# EXP_GameDuino_V1.net
KiCad netlist of a schematic drawn in EAGLE
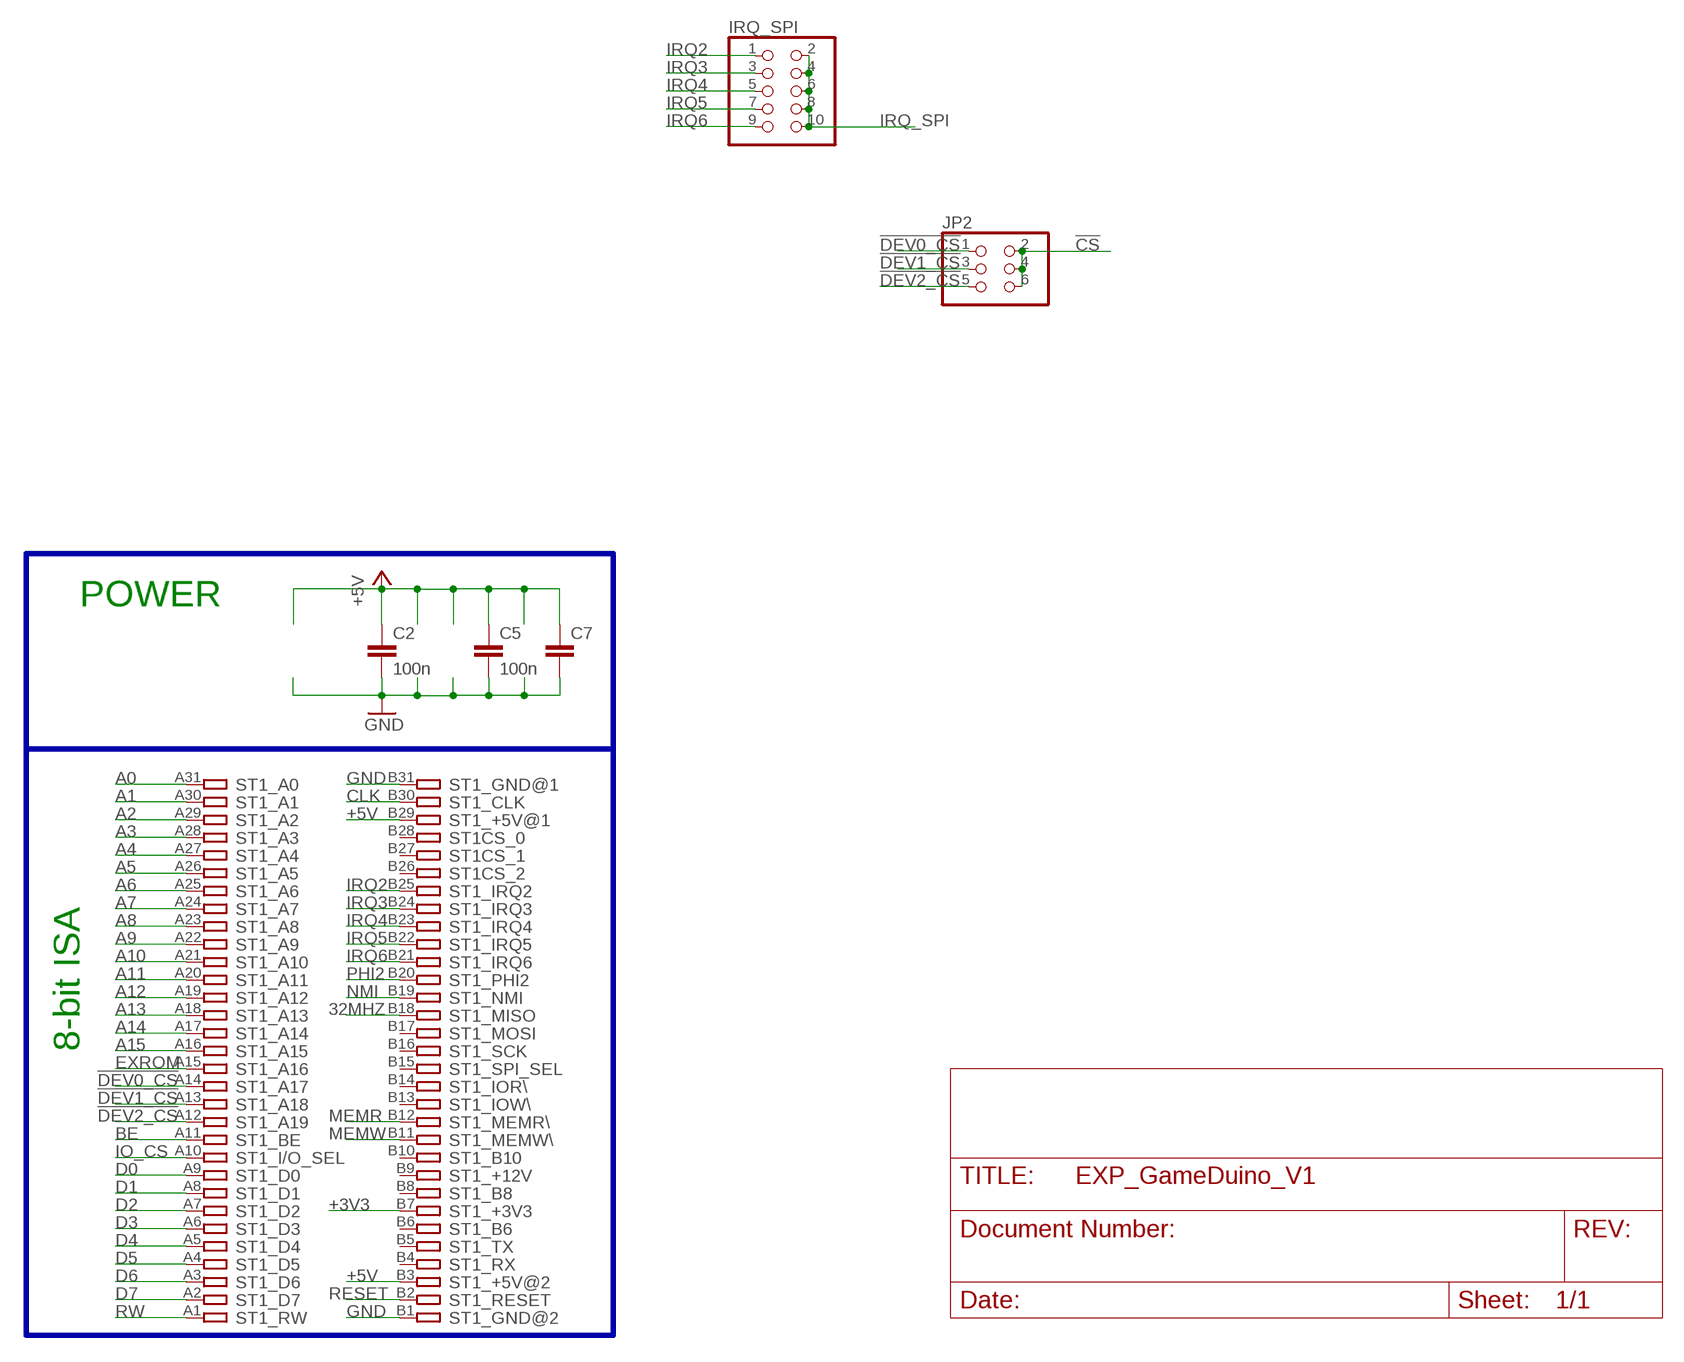
[diagram p0: schematic, sheet 1, part 1 of 2]
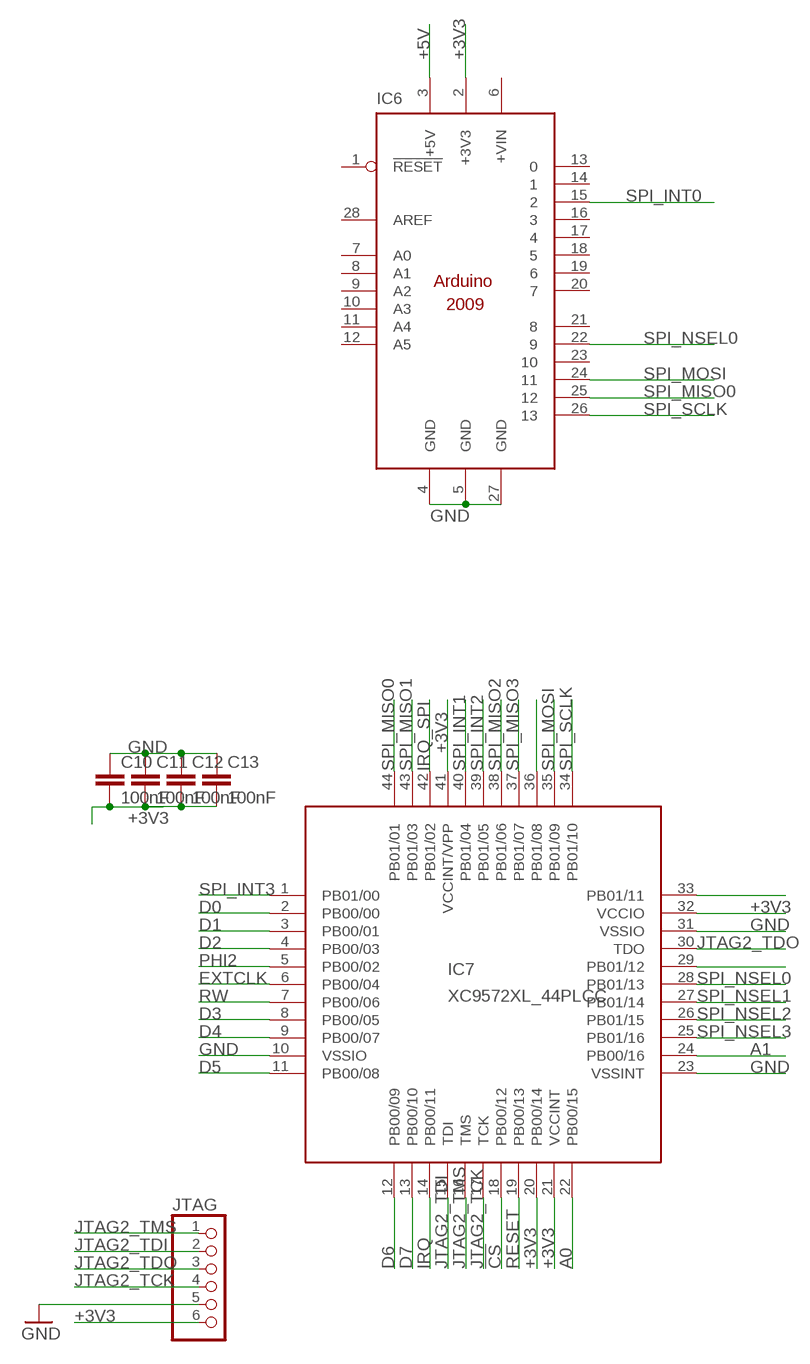
[diagram p1: schematic, sheet 1, part 2 of 2]

(export (version "E")
  (design (tool "Eeschema 10.0.6"))
  (components
    (comp (ref "C2")
      (value "100n")
      (footprint "eagle-import:C050-025X075")
      (libsource (lib "eagle-import") (part "C-EU050-025X075"))
    )
    (comp (ref "C5")
      (value "100n")
      (footprint "eagle-import:C050-025X075")
      (libsource (lib "eagle-import") (part "C-EU050-025X075"))
    )
    (comp (ref "C7")
      (value "C-EU050-035X075")
      (footprint "eagle-import:C050-035X075")
      (libsource (lib "eagle-import") (part "rcl_334_C-EU050-035X075"))
    )
    (comp (ref "C10")
      (value "100nF")
      (footprint "eagle-import:C603")
      (libsource (lib "eagle-import") (part "CAPC603"))
    )
    (comp (ref "C11")
      (value "100nF")
      (footprint "eagle-import:C603")
      (libsource (lib "eagle-import") (part "CAPC603"))
    )
    (comp (ref "C12")
      (value "100nF")
      (footprint "eagle-import:C603")
      (libsource (lib "eagle-import") (part "CAPC603"))
    )
    (comp (ref "C13")
      (value "100nF")
      (footprint "eagle-import:C603")
      (libsource (lib "eagle-import") (part "CAPC603"))
    )
    (comp (ref "IC6")
      (value "ARDUINO2009_10")
      (footprint "eagle-import:ARDUINO2009")
      (libsource (lib "eagle-import") (part "ARDUINO2009_10"))
    )
    (comp (ref "IC7")
      (value "XC9572XL_44PLCC")
      (footprint "eagle-import:S44")
      (libsource (lib "eagle-import") (part "XC9536_44PLCCPLCC44_THT"))
    )
    (comp (ref "IRQ_SPI")
      (value "PINHD-2X5")
      (footprint "eagle-import:2X05")
      (libsource (lib "eagle-import") (part "PINHD-2X5"))
    )
    (comp (ref "JP2")
      (value "PINHD-2X3")
      (footprint "eagle-import:2X03")
      (libsource (lib "eagle-import") (part "PINHD-2X3"))
    )
    (comp (ref "JTAG")
      (value "PINHD-1X6")
      (footprint "eagle-import:1X06")
      (libsource (lib "eagle-import") (part "PINHD-1X6"))
    )
    (comp (ref "ST1")
      (value "IBM8BIT_ISASHORT")
      (footprint "eagle-import:APP_2X32_SHORT")
      (libsource (lib "eagle-import") (part "IBM8BIT_ISASHORT"))
    )
  )
  (nets
    (net (code "1") (name "+5V") (class "Default")
      (node (ref "C2") (pin "1") (pinfunction "1_1") (pintype "passive"))
      (node (ref "C5") (pin "1") (pinfunction "1_1") (pintype "passive"))
      (node (ref "C7") (pin "1") (pinfunction "1_1") (pintype "passive"))
      (node (ref "IC6") (pin "3") (pinfunction "+5V_3") (pintype "power_in"))
      (node (ref "ST1") (pin "B29") (pinfunction "P_B29") (pintype "bidirectional"))
      (node (ref "ST1") (pin "B3") (pinfunction "P_B3") (pintype "bidirectional"))
    )
    (net (code "2") (name "/+3V3") (class "Default")
      (node (ref "C10") (pin "2") (pinfunction "2_2") (pintype "passive"))
      (node (ref "C11") (pin "2") (pinfunction "2_2") (pintype "passive"))
      (node (ref "C12") (pin "2") (pinfunction "2_2") (pintype "passive"))
      (node (ref "C13") (pin "2") (pinfunction "2_2") (pintype "passive"))
      (node (ref "IC6") (pin "2") (pinfunction "+3V3_2") (pintype "power_in"))
      (node (ref "IC7") (pin "20") (pinfunction "PB00/14_20") (pintype "bidirectional"))
      (node (ref "IC7") (pin "21") (pinfunction "VCCINT_21") (pintype "power_in"))
      (node (ref "IC7") (pin "32") (pinfunction "VCCIO_32") (pintype "power_in"))
      (node (ref "IC7") (pin "41") (pinfunction "VCCINT/VPP_41") (pintype "input"))
      (node (ref "JTAG") (pin "6") (pinfunction "6_6") (pintype "passive"))
      (node (ref "ST1") (pin "B7") (pinfunction "P_B7") (pintype "bidirectional"))
    )
    (net (code "3") (name "/32MHZ") (class "Default")
      (node (ref "ST1") (pin "B18") (pinfunction "P_B18") (pintype "bidirectional"))
    )
    (net (code "4") (name "/A0") (class "Default")
      (node (ref "IC7") (pin "22") (pinfunction "PB00/15_22") (pintype "bidirectional"))
      (node (ref "ST1") (pin "A31") (pinfunction "P_A31") (pintype "bidirectional"))
    )
    (net (code "5") (name "/A1") (class "Default")
      (node (ref "IC7") (pin "24") (pinfunction "PB00/16_24") (pintype "bidirectional"))
      (node (ref "ST1") (pin "A30") (pinfunction "P_A30") (pintype "bidirectional"))
    )
    (net (code "6") (name "/A2") (class "Default")
      (node (ref "ST1") (pin "A29") (pinfunction "P_A29") (pintype "bidirectional"))
    )
    (net (code "7") (name "/A3") (class "Default")
      (node (ref "ST1") (pin "A28") (pinfunction "P_A28") (pintype "bidirectional"))
    )
    (net (code "8") (name "/A4") (class "Default")
      (node (ref "ST1") (pin "A27") (pinfunction "P_A27") (pintype "bidirectional"))
    )
    (net (code "9") (name "/A5") (class "Default")
      (node (ref "ST1") (pin "A26") (pinfunction "P_A26") (pintype "bidirectional"))
    )
    (net (code "10") (name "/A6") (class "Default")
      (node (ref "ST1") (pin "A25") (pinfunction "P_A25") (pintype "bidirectional"))
    )
    (net (code "11") (name "/A7") (class "Default")
      (node (ref "ST1") (pin "A24") (pinfunction "P_A24") (pintype "bidirectional"))
    )
    (net (code "12") (name "/A8") (class "Default")
      (node (ref "ST1") (pin "A23") (pinfunction "P_A23") (pintype "bidirectional"))
    )
    (net (code "13") (name "/A9") (class "Default")
      (node (ref "ST1") (pin "A22") (pinfunction "P_A22") (pintype "bidirectional"))
    )
    (net (code "14") (name "/A10") (class "Default")
      (node (ref "ST1") (pin "A21") (pinfunction "P_A21") (pintype "bidirectional"))
    )
    (net (code "15") (name "/A11") (class "Default")
      (node (ref "ST1") (pin "A20") (pinfunction "P_A20") (pintype "bidirectional"))
    )
    (net (code "16") (name "/A12") (class "Default")
      (node (ref "ST1") (pin "A19") (pinfunction "P_A19") (pintype "bidirectional"))
    )
    (net (code "17") (name "/A13") (class "Default")
      (node (ref "ST1") (pin "A18") (pinfunction "P_A18") (pintype "bidirectional"))
    )
    (net (code "18") (name "/A14") (class "Default")
      (node (ref "ST1") (pin "A17") (pinfunction "P_A17") (pintype "bidirectional"))
    )
    (net (code "19") (name "/A15") (class "Default")
      (node (ref "ST1") (pin "A16") (pinfunction "P_A16") (pintype "bidirectional"))
    )
    (net (code "20") (name "/BE") (class "Default")
      (node (ref "ST1") (pin "A11") (pinfunction "P_A11") (pintype "bidirectional"))
    )
    (net (code "21") (name "/CLK") (class "Default")
      (node (ref "ST1") (pin "B30") (pinfunction "P_B30") (pintype "bidirectional"))
    )
    (net (code "22") (name "/D0") (class "Default")
      (node (ref "IC7") (pin "2") (pinfunction "PB00/00_2") (pintype "bidirectional"))
      (node (ref "ST1") (pin "A9") (pinfunction "P_A9") (pintype "bidirectional"))
    )
    (net (code "23") (name "/D1") (class "Default")
      (node (ref "IC7") (pin "3") (pinfunction "PB00/01_3") (pintype "bidirectional"))
      (node (ref "ST1") (pin "A8") (pinfunction "P_A8") (pintype "bidirectional"))
    )
    (net (code "24") (name "/D2") (class "Default")
      (node (ref "IC7") (pin "4") (pinfunction "PB00/03_4") (pintype "bidirectional"))
      (node (ref "ST1") (pin "A7") (pinfunction "P_A7") (pintype "bidirectional"))
    )
    (net (code "25") (name "/D3") (class "Default")
      (node (ref "IC7") (pin "8") (pinfunction "PB00/05_8") (pintype "bidirectional"))
      (node (ref "ST1") (pin "A6") (pinfunction "P_A6") (pintype "bidirectional"))
    )
    (net (code "26") (name "/D4") (class "Default")
      (node (ref "IC7") (pin "9") (pinfunction "PB00/07_9") (pintype "bidirectional"))
      (node (ref "ST1") (pin "A5") (pinfunction "P_A5") (pintype "bidirectional"))
    )
    (net (code "27") (name "/D5") (class "Default")
      (node (ref "IC7") (pin "11") (pinfunction "PB00/08_11") (pintype "bidirectional"))
      (node (ref "ST1") (pin "A4") (pinfunction "P_A4") (pintype "bidirectional"))
    )
    (net (code "28") (name "/D6") (class "Default")
      (node (ref "IC7") (pin "12") (pinfunction "PB00/09_12") (pintype "bidirectional"))
      (node (ref "ST1") (pin "A3") (pinfunction "P_A3") (pintype "bidirectional"))
    )
    (net (code "29") (name "/D7") (class "Default")
      (node (ref "IC7") (pin "13") (pinfunction "PB00/10_13") (pintype "bidirectional"))
      (node (ref "ST1") (pin "A2") (pinfunction "P_A2") (pintype "bidirectional"))
    )
    (net (code "30") (name "/EXROM") (class "Default")
      (node (ref "ST1") (pin "A15") (pinfunction "P_A15") (pintype "bidirectional"))
    )
    (net (code "31") (name "/EXTCLK") (class "Default")
      (node (ref "IC7") (pin "6") (pinfunction "PB00/04_6") (pintype "bidirectional"))
    )
    (net (code "32") (name "/IO_CS") (class "Default")
      (node (ref "ST1") (pin "A10") (pinfunction "P_A10") (pintype "bidirectional"))
    )
    (net (code "33") (name "/IRQ") (class "Default")
      (node (ref "IC7") (pin "14") (pinfunction "PB00/11_14") (pintype "bidirectional"))
    )
    (net (code "34") (name "/IRQ2") (class "Default")
      (node (ref "IRQ_SPI") (pin "1") (pinfunction "1_1") (pintype "passive"))
      (node (ref "ST1") (pin "B25") (pinfunction "P_B25") (pintype "bidirectional"))
    )
    (net (code "35") (name "/IRQ3") (class "Default")
      (node (ref "IRQ_SPI") (pin "3") (pinfunction "3_3") (pintype "passive"))
      (node (ref "ST1") (pin "B24") (pinfunction "P_B24") (pintype "bidirectional"))
    )
    (net (code "36") (name "/IRQ4") (class "Default")
      (node (ref "IRQ_SPI") (pin "5") (pinfunction "5_5") (pintype "passive"))
      (node (ref "ST1") (pin "B23") (pinfunction "P_B23") (pintype "bidirectional"))
    )
    (net (code "37") (name "/IRQ5") (class "Default")
      (node (ref "IRQ_SPI") (pin "7") (pinfunction "7_7") (pintype "passive"))
      (node (ref "ST1") (pin "B22") (pinfunction "P_B22") (pintype "bidirectional"))
    )
    (net (code "38") (name "/IRQ6") (class "Default")
      (node (ref "IRQ_SPI") (pin "9") (pinfunction "9_9") (pintype "passive"))
      (node (ref "ST1") (pin "B21") (pinfunction "P_B21") (pintype "bidirectional"))
    )
    (net (code "39") (name "/IRQ_SPI") (class "Default")
      (node (ref "IC7") (pin "42") (pinfunction "PB01/02_42") (pintype "bidirectional"))
      (node (ref "IRQ_SPI") (pin "10") (pinfunction "10_10") (pintype "passive"))
      (node (ref "IRQ_SPI") (pin "2") (pinfunction "2_2") (pintype "passive"))
      (node (ref "IRQ_SPI") (pin "4") (pinfunction "4_4") (pintype "passive"))
      (node (ref "IRQ_SPI") (pin "6") (pinfunction "6_6") (pintype "passive"))
      (node (ref "IRQ_SPI") (pin "8") (pinfunction "8_8") (pintype "passive"))
    )
    (net (code "40") (name "/JTAG2_TCK") (class "Default")
      (node (ref "IC7") (pin "17") (pinfunction "TCK_17") (pintype "input"))
      (node (ref "JTAG") (pin "4") (pinfunction "4_4") (pintype "passive"))
    )
    (net (code "41") (name "/JTAG2_TDI") (class "Default")
      (node (ref "IC7") (pin "15") (pinfunction "TDI_15") (pintype "input"))
      (node (ref "JTAG") (pin "2") (pinfunction "2_2") (pintype "passive"))
    )
    (net (code "42") (name "/JTAG2_TDO") (class "Default")
      (node (ref "IC7") (pin "30") (pinfunction "TDO_30") (pintype "output"))
      (node (ref "JTAG") (pin "3") (pinfunction "3_3") (pintype "passive"))
    )
    (net (code "43") (name "/JTAG2_TMS") (class "Default")
      (node (ref "IC7") (pin "16") (pinfunction "TMS_16") (pintype "input"))
      (node (ref "JTAG") (pin "1") (pinfunction "1_1") (pintype "passive"))
    )
    (net (code "44") (name "/MEMR") (class "Default")
      (node (ref "ST1") (pin "B12") (pinfunction "P_B12") (pintype "bidirectional"))
    )
    (net (code "45") (name "/MEMW") (class "Default")
      (node (ref "ST1") (pin "B11") (pinfunction "P_B11") (pintype "bidirectional"))
    )
    (net (code "46") (name "/NMI") (class "Default")
      (node (ref "ST1") (pin "B19") (pinfunction "P_B19") (pintype "bidirectional"))
    )
    (net (code "47") (name "/PHI2") (class "Default")
      (node (ref "IC7") (pin "5") (pinfunction "PB00/02_5") (pintype "bidirectional"))
      (node (ref "ST1") (pin "B20") (pinfunction "P_B20") (pintype "bidirectional"))
    )
    (net (code "48") (name "/RESET") (class "Default")
      (node (ref "IC7") (pin "19") (pinfunction "PB00/13_19") (pintype "bidirectional"))
      (node (ref "ST1") (pin "B2") (pinfunction "P_B2") (pintype "bidirectional"))
    )
    (net (code "49") (name "/RW") (class "Default")
      (node (ref "IC7") (pin "7") (pinfunction "PB00/06_7") (pintype "bidirectional"))
      (node (ref "ST1") (pin "A1") (pinfunction "P_A1") (pintype "bidirectional"))
    )
    (net (code "50") (name "/SPI_INT0") (class "Default")
      (node (ref "IC6") (pin "15") (pinfunction "2_15") (pintype "bidirectional"))
    )
    (net (code "51") (name "/SPI_INT1") (class "Default")
      (node (ref "IC7") (pin "40") (pinfunction "PB01/04_40") (pintype "bidirectional"))
    )
    (net (code "52") (name "/SPI_INT2") (class "Default")
      (node (ref "IC7") (pin "39") (pinfunction "PB01/05_39") (pintype "bidirectional"))
    )
    (net (code "53") (name "/SPI_INT3") (class "Default")
      (node (ref "IC7") (pin "1") (pinfunction "PB01/00_1") (pintype "bidirectional"))
    )
    (net (code "54") (name "/SPI_MISO0") (class "Default")
      (node (ref "IC6") (pin "25") (pinfunction "12_25") (pintype "bidirectional"))
      (node (ref "IC7") (pin "44") (pinfunction "PB01/01_44") (pintype "bidirectional"))
    )
    (net (code "55") (name "/SPI_MISO1") (class "Default")
      (node (ref "IC7") (pin "43") (pinfunction "PB01/03_43") (pintype "bidirectional"))
    )
    (net (code "56") (name "/SPI_MISO2") (class "Default")
      (node (ref "IC7") (pin "38") (pinfunction "PB01/06_38") (pintype "bidirectional"))
    )
    (net (code "57") (name "/SPI_MISO3") (class "Default")
      (node (ref "IC7") (pin "37") (pinfunction "PB01/07_37") (pintype "bidirectional"))
    )
    (net (code "58") (name "/SPI_MOSI") (class "Default")
      (node (ref "IC6") (pin "24") (pinfunction "11_24") (pintype "bidirectional"))
      (node (ref "IC7") (pin "35") (pinfunction "PB01/09_35") (pintype "bidirectional"))
    )
    (net (code "59") (name "/SPI_NSEL0") (class "Default")
      (node (ref "IC6") (pin "22") (pinfunction "9_22") (pintype "bidirectional"))
      (node (ref "IC7") (pin "28") (pinfunction "PB01/13_28") (pintype "bidirectional"))
    )
    (net (code "60") (name "/SPI_NSEL1") (class "Default")
      (node (ref "IC7") (pin "27") (pinfunction "PB01/14_27") (pintype "bidirectional"))
    )
    (net (code "61") (name "/SPI_NSEL2") (class "Default")
      (node (ref "IC7") (pin "26") (pinfunction "PB01/15_26") (pintype "bidirectional"))
    )
    (net (code "62") (name "/SPI_NSEL3") (class "Default")
      (node (ref "IC7") (pin "25") (pinfunction "PB01/16_25") (pintype "bidirectional"))
    )
    (net (code "63") (name "/SPI_SCLK") (class "Default")
      (node (ref "IC6") (pin "26") (pinfunction "13_26") (pintype "bidirectional"))
      (node (ref "IC7") (pin "34") (pinfunction "PB01/10_34") (pintype "bidirectional"))
    )
    (net (code "64") (name "/~{CS}") (class "Default")
      (node (ref "IC7") (pin "18") (pinfunction "PB00/12_18") (pintype "bidirectional"))
      (node (ref "JP2") (pin "2") (pinfunction "2_2") (pintype "passive"))
      (node (ref "JP2") (pin "4") (pinfunction "4_4") (pintype "passive"))
      (node (ref "JP2") (pin "6") (pinfunction "6_6") (pintype "passive"))
    )
    (net (code "65") (name "/~{DEV0_CS}") (class "Default")
      (node (ref "JP2") (pin "1") (pinfunction "1_1") (pintype "passive"))
      (node (ref "ST1") (pin "A14") (pinfunction "P_A14") (pintype "bidirectional"))
    )
    (net (code "66") (name "/~{DEV1_CS}") (class "Default")
      (node (ref "JP2") (pin "3") (pinfunction "3_3") (pintype "passive"))
      (node (ref "ST1") (pin "A13") (pinfunction "P_A13") (pintype "bidirectional"))
    )
    (net (code "67") (name "/~{DEV2_CS}") (class "Default")
      (node (ref "JP2") (pin "5") (pinfunction "5_5") (pintype "passive"))
      (node (ref "ST1") (pin "A12") (pinfunction "P_A12") (pintype "bidirectional"))
    )
    (net (code "68") (name "GND") (class "Default")
      (node (ref "C10") (pin "1") (pinfunction "1_1") (pintype "passive"))
      (node (ref "C11") (pin "1") (pinfunction "1_1") (pintype "passive"))
      (node (ref "C12") (pin "1") (pinfunction "1_1") (pintype "passive"))
      (node (ref "C13") (pin "1") (pinfunction "1_1") (pintype "passive"))
      (node (ref "C2") (pin "2") (pinfunction "2_2") (pintype "passive"))
      (node (ref "C5") (pin "2") (pinfunction "2_2") (pintype "passive"))
      (node (ref "C7") (pin "2") (pinfunction "2_2") (pintype "passive"))
      (node (ref "IC6") (pin "27") (pinfunction "GND_27") (pintype "power_in"))
      (node (ref "IC6") (pin "4") (pinfunction "GND_4") (pintype "power_in"))
      (node (ref "IC6") (pin "5") (pinfunction "GND_5") (pintype "power_in"))
      (node (ref "IC7") (pin "10") (pinfunction "VSSIO_10") (pintype "power_in"))
      (node (ref "IC7") (pin "23") (pinfunction "VSSINT_23") (pintype "power_in"))
      (node (ref "IC7") (pin "31") (pinfunction "VSSIO_31") (pintype "power_in"))
      (node (ref "JTAG") (pin "5") (pinfunction "5_5") (pintype "passive"))
      (node (ref "ST1") (pin "B1") (pinfunction "P_B1") (pintype "bidirectional"))
      (node (ref "ST1") (pin "B31") (pinfunction "P_B31") (pintype "bidirectional"))
    )
    (net (code "69") (name "unconnected-(IC6-+VIN-Pad6)") (class "Default")
      (node (ref "IC6") (pin "6") (pinfunction "+VIN_6") (pintype "bidirectional"))
    )
    (net (code "70") (name "unconnected-(IC6-0-Pad13)") (class "Default")
      (node (ref "IC6") (pin "13") (pinfunction "0_13") (pintype "bidirectional"))
    )
    (net (code "71") (name "unconnected-(IC6-1-Pad14)") (class "Default")
      (node (ref "IC6") (pin "14") (pinfunction "1_14") (pintype "bidirectional"))
    )
    (net (code "72") (name "unconnected-(IC6-3-Pad16)") (class "Default")
      (node (ref "IC6") (pin "16") (pinfunction "3_16") (pintype "bidirectional"))
    )
    (net (code "73") (name "unconnected-(IC6-4-Pad17)") (class "Default")
      (node (ref "IC6") (pin "17") (pinfunction "4_17") (pintype "bidirectional"))
    )
    (net (code "74") (name "unconnected-(IC6-5-Pad18)") (class "Default")
      (node (ref "IC6") (pin "18") (pinfunction "5_18") (pintype "bidirectional"))
    )
    (net (code "75") (name "unconnected-(IC6-6-Pad19)") (class "Default")
      (node (ref "IC6") (pin "19") (pinfunction "6_19") (pintype "bidirectional"))
    )
    (net (code "76") (name "unconnected-(IC6-7-Pad20)") (class "Default")
      (node (ref "IC6") (pin "20") (pinfunction "7_20") (pintype "bidirectional"))
    )
    (net (code "77") (name "unconnected-(IC6-8-Pad21)") (class "Default")
      (node (ref "IC6") (pin "21") (pinfunction "8_21") (pintype "bidirectional"))
    )
    (net (code "78") (name "unconnected-(IC6-10-Pad23)") (class "Default")
      (node (ref "IC6") (pin "23") (pinfunction "10_23") (pintype "bidirectional"))
    )
    (net (code "79") (name "unconnected-(IC6-A0-Pad7)") (class "Default")
      (node (ref "IC6") (pin "7") (pinfunction "A0_7") (pintype "bidirectional"))
    )
    (net (code "80") (name "unconnected-(IC6-A1-Pad8)") (class "Default")
      (node (ref "IC6") (pin "8") (pinfunction "A1_8") (pintype "bidirectional"))
    )
    (net (code "81") (name "unconnected-(IC6-A2-Pad9)") (class "Default")
      (node (ref "IC6") (pin "9") (pinfunction "A2_9") (pintype "bidirectional"))
    )
    (net (code "82") (name "unconnected-(IC6-A3-Pad10)") (class "Default")
      (node (ref "IC6") (pin "10") (pinfunction "A3_10") (pintype "bidirectional"))
    )
    (net (code "83") (name "unconnected-(IC6-A4-Pad11)") (class "Default")
      (node (ref "IC6") (pin "11") (pinfunction "A4_11") (pintype "bidirectional"))
    )
    (net (code "84") (name "unconnected-(IC6-A5-Pad12)") (class "Default")
      (node (ref "IC6") (pin "12") (pinfunction "A5_12") (pintype "bidirectional"))
    )
    (net (code "85") (name "unconnected-(IC6-AREF-Pad28)") (class "Default")
      (node (ref "IC6") (pin "28") (pinfunction "AREF_28") (pintype "bidirectional"))
    )
    (net (code "86") (name "unconnected-(IC6-~{RESET}-Pad1)") (class "Default")
      (node (ref "IC6") (pin "1") (pinfunction "~{RESET}_1") (pintype "bidirectional"))
    )
    (net (code "87") (name "unconnected-(IC7-PB01{slash}08-Pad36)") (class "Default")
      (node (ref "IC7") (pin "36") (pinfunction "PB01/08_36") (pintype "bidirectional"))
    )
    (net (code "88") (name "unconnected-(IC7-PB01{slash}11-Pad33)") (class "Default")
      (node (ref "IC7") (pin "33") (pinfunction "PB01/11_33") (pintype "bidirectional"))
    )
    (net (code "89") (name "unconnected-(IC7-PB01{slash}12-Pad29)") (class "Default")
      (node (ref "IC7") (pin "29") (pinfunction "PB01/12_29") (pintype "bidirectional"))
    )
    (net (code "90") (name "unconnected-(ST1A-P-PadB28)") (class "Default")
      (node (ref "ST1") (pin "B28") (pinfunction "P_B28") (pintype "bidirectional"))
    )
    (net (code "91") (name "unconnected-(ST1AB-P-PadB10)") (class "Default")
      (node (ref "ST1") (pin "B10") (pinfunction "P_B10") (pintype "bidirectional"))
    )
    (net (code "92") (name "unconnected-(ST1AC-P-PadB6)") (class "Default")
      (node (ref "ST1") (pin "B6") (pinfunction "P_B6") (pintype "bidirectional"))
    )
    (net (code "93") (name "unconnected-(ST1AD-P-PadB8)") (class "Default")
      (node (ref "ST1") (pin "B8") (pinfunction "P_B8") (pintype "bidirectional"))
    )
    (net (code "94") (name "unconnected-(ST1AR-P-PadB14)") (class "Default")
      (node (ref "ST1") (pin "B14") (pinfunction "P_B14") (pintype "bidirectional"))
    )
    (net (code "95") (name "unconnected-(ST1AS-P-PadB13)") (class "Default")
      (node (ref "ST1") (pin "B13") (pinfunction "P_B13") (pintype "bidirectional"))
    )
    (net (code "96") (name "unconnected-(ST1B-P-PadB27)") (class "Default")
      (node (ref "ST1") (pin "B27") (pinfunction "P_B27") (pintype "bidirectional"))
    )
    (net (code "97") (name "unconnected-(ST1BB-P-PadB17)") (class "Default")
      (node (ref "ST1") (pin "B17") (pinfunction "P_B17") (pintype "bidirectional"))
    )
    (net (code "98") (name "unconnected-(ST1BG-P-PadB4)") (class "Default")
      (node (ref "ST1") (pin "B4") (pinfunction "P_B4") (pintype "bidirectional"))
    )
    (net (code "99") (name "unconnected-(ST1BH-P-PadB16)") (class "Default")
      (node (ref "ST1") (pin "B16") (pinfunction "P_B16") (pintype "bidirectional"))
    )
    (net (code "100") (name "unconnected-(ST1BI-P-PadB15)") (class "Default")
      (node (ref "ST1") (pin "B15") (pinfunction "P_B15") (pintype "bidirectional"))
    )
    (net (code "101") (name "unconnected-(ST1BJ-P-PadB5)") (class "Default")
      (node (ref "ST1") (pin "B5") (pinfunction "P_B5") (pintype "bidirectional"))
    )
    (net (code "102") (name "unconnected-(ST1C-P-PadB26)") (class "Default")
      (node (ref "ST1") (pin "B26") (pinfunction "P_B26") (pintype "bidirectional"))
    )
    (net (code "103") (name "unconnected-(ST1D-P-PadB9)") (class "Default")
      (node (ref "ST1") (pin "B9") (pinfunction "P_B9") (pintype "bidirectional"))
    )
  )
)
